# Sheet1.net
KiCad netlist of a schematic drawn in Altium Designer
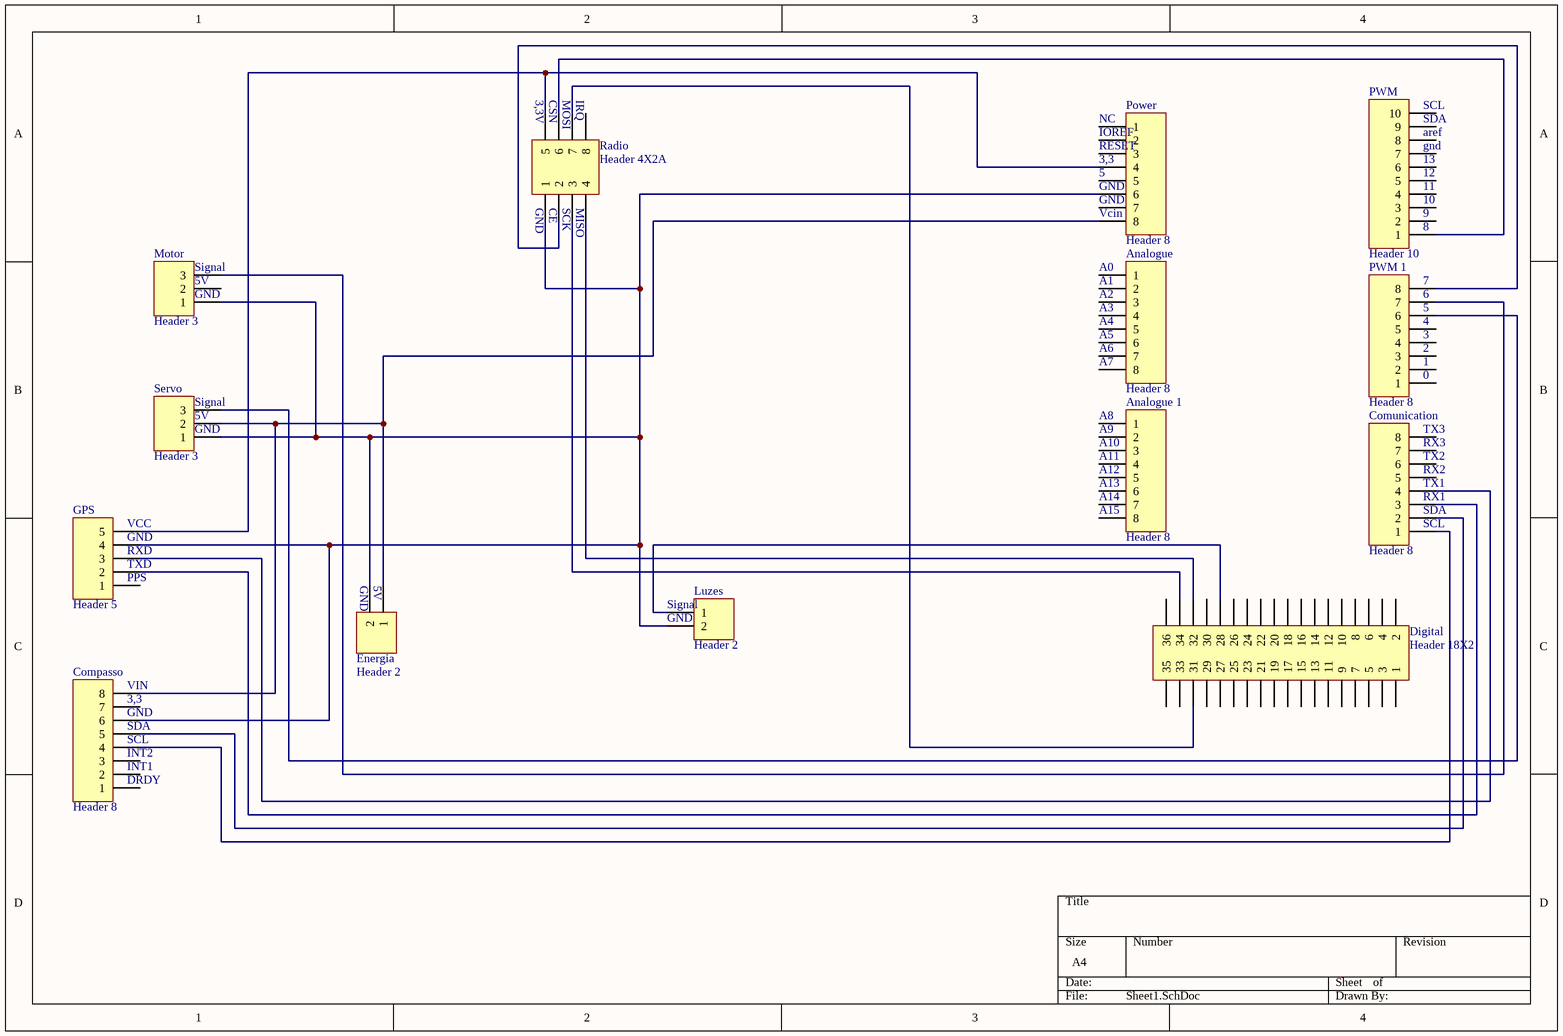
[diagram p0: Sheet1.SchDoc]

(export (version "E")
  (design (tool "Eeschema 10.0.6"))
  (components
    (comp (ref "Analogue")
      (value "Header 8")
      (footprint "HDR1X8")
      (description "Header, 8-Pin")
      (fields (field (name "PUBLISHER") "Altium Limited"))
      (libsource (lib "") (part "Header 8_1"))
    )
    (comp (ref "Analogue 1")
      (value "Header 8")
      (footprint "HDR1X8")
      (description "Header, 8-Pin")
      (fields (field (name "PUBLISHER") "Altium Limited"))
      (libsource (lib "") (part "Header 8_1"))
    )
    (comp (ref "Compasso")
      (value "Header 8")
      (footprint "HDR1X8")
      (description "Header, 8-Pin")
      (fields (field (name "PUBLISHER") "Altium Limited"))
      (libsource (lib "Miscellaneous Connectors") (part "Header 8"))
    )
    (comp (ref "Comunication")
      (value "Header 8")
      (footprint "HDR1X8")
      (description "Header, 8-Pin")
      (fields (field (name "PUBLISHER") "Altium Limited"))
      (libsource (lib "Miscellaneous Connectors") (part "Header 8"))
    )
    (comp (ref "Digital")
      (value "Header 18X2")
      (footprint "HDR2X18")
      (description "Header, 18-Pin, Dual row")
      (fields (field (name "PUBLISHER") "Altium Limited"))
      (libsource (lib "Miscellaneous Connectors") (part "Header 18X2"))
    )
    (comp (ref "Energia")
      (value "Header 2")
      (footprint "HDR1X2")
      (description "Header, 2-Pin")
      (fields (field (name "PUBLISHER") "Altium Limited"))
      (libsource (lib "") (part "Header 2_1"))
    )
    (comp (ref "GPS")
      (value "Header 5")
      (footprint "HDR1X5")
      (description "Header, 5-Pin")
      (fields (field (name "PUBLISHER") "Altium Limited"))
      (libsource (lib "Miscellaneous Connectors") (part "Header 5"))
    )
    (comp (ref "Luzes")
      (value "Header 2")
      (footprint "HDR1X2")
      (description "Header, 2-Pin")
      (fields (field (name "PUBLISHER") "Altium Limited"))
      (libsource (lib "Miscellaneous Connectors") (part "Header 2"))
    )
    (comp (ref "Motor")
      (value "Header 3")
      (footprint "HDR1X3")
      (description "Header, 3-Pin")
      (fields (field (name "PUBLISHER") "Altium Limited"))
      (libsource (lib "Miscellaneous Connectors") (part "Header 3"))
    )
    (comp (ref "Power")
      (value "Header 8")
      (footprint "HDR1X8")
      (description "Header, 8-Pin")
      (fields (field (name "PUBLISHER") "Altium Limited"))
      (libsource (lib "") (part "Header 8_1"))
    )
    (comp (ref "PWM")
      (value "Header 10")
      (footprint "HDR1X10")
      (description "Header, 10-Pin")
      (fields (field (name "PUBLISHER") "Altium Limited"))
      (libsource (lib "Miscellaneous Connectors") (part "Header 10"))
    )
    (comp (ref "PWM 1")
      (value "Header 8")
      (footprint "HDR1X8")
      (description "Header, 8-Pin")
      (fields (field (name "PUBLISHER") "Altium Limited"))
      (libsource (lib "Miscellaneous Connectors") (part "Header 8"))
    )
    (comp (ref "Radio")
      (value "Header 4X2A")
      (footprint "HDR2X4_CEN")
      (description "Header, 4-Pin, Dual row")
      (fields (field (name "PUBLISHER") "Altium Limited"))
      (libsource (lib "Miscellaneous Connectors") (part "Header 4X2A"))
    )
    (comp (ref "Servo")
      (value "Header 3")
      (footprint "HDR1X3")
      (description "Header, 3-Pin")
      (fields (field (name "PUBLISHER") "Altium Limited"))
      (libsource (lib "Miscellaneous Connectors") (part "Header 3"))
    )
  )
  (nets
    (net (code "1") (name "Net-(Compasso-Pad4)") (class "Default")
      (node (ref "Compasso") (pin "4") (pinfunction "4_4") (pintype "passive"))
      (node (ref "Comunication") (pin "1") (pinfunction "1_1") (pintype "passive"))
    )
    (net (code "2") (name "Net-(Compasso-Pad5)") (class "Default")
      (node (ref "Compasso") (pin "5") (pinfunction "5_5") (pintype "passive"))
      (node (ref "Comunication") (pin "2") (pinfunction "2_2") (pintype "passive"))
    )
    (net (code "3") (name "Net-(Compasso-Pad6)") (class "Default")
      (node (ref "Compasso") (pin "6") (pinfunction "6_6") (pintype "passive"))
      (node (ref "Energia") (pin "2") (pinfunction "2_2") (pintype "passive"))
      (node (ref "GPS") (pin "4") (pinfunction "4_4") (pintype "passive"))
      (node (ref "Luzes") (pin "2") (pinfunction "2_2") (pintype "passive"))
      (node (ref "Motor") (pin "1") (pinfunction "1_1") (pintype "passive"))
      (node (ref "Power") (pin "6") (pinfunction "6_6") (pintype "passive"))
      (node (ref "Radio") (pin "1") (pinfunction "1_1") (pintype "passive"))
      (node (ref "Servo") (pin "1") (pinfunction "1_1") (pintype "passive"))
    )
    (net (code "4") (name "Net-(Compasso-Pad8)") (class "Default")
      (node (ref "Compasso") (pin "8") (pinfunction "8_8") (pintype "passive"))
      (node (ref "Energia") (pin "1") (pinfunction "1_1") (pintype "passive"))
      (node (ref "Power") (pin "8") (pinfunction "8_8") (pintype "passive"))
      (node (ref "Servo") (pin "2") (pinfunction "2_2") (pintype "passive"))
    )
    (net (code "5") (name "Net-(Comunication-Pad3)") (class "Default")
      (node (ref "Comunication") (pin "3") (pinfunction "3_3") (pintype "passive"))
      (node (ref "GPS") (pin "2") (pinfunction "2_2") (pintype "passive"))
    )
    (net (code "6") (name "Net-(Comunication-Pad4)") (class "Default")
      (node (ref "Comunication") (pin "4") (pinfunction "4_4") (pintype "passive"))
      (node (ref "GPS") (pin "3") (pinfunction "3_3") (pintype "passive"))
    )
    (net (code "7") (name "Net-(Digital-Pad28)") (class "Default")
      (node (ref "Digital") (pin "28") (pinfunction "28_28") (pintype "passive"))
      (node (ref "Luzes") (pin "1") (pinfunction "1_1") (pintype "passive"))
    )
    (net (code "8") (name "Net-(Digital-Pad31)") (class "Default")
      (node (ref "Digital") (pin "31") (pinfunction "31_31") (pintype "passive"))
      (node (ref "Radio") (pin "7") (pinfunction "7_7") (pintype "passive"))
    )
    (net (code "9") (name "Net-(Digital-Pad32)") (class "Default")
      (node (ref "Digital") (pin "32") (pinfunction "32_32") (pintype "passive"))
      (node (ref "Radio") (pin "4") (pinfunction "4_4") (pintype "passive"))
    )
    (net (code "10") (name "Net-(Digital-Pad34)") (class "Default")
      (node (ref "Digital") (pin "34") (pinfunction "34_34") (pintype "passive"))
      (node (ref "Radio") (pin "3") (pinfunction "3_3") (pintype "passive"))
    )
    (net (code "11") (name "Net-(GPS-Pad5)") (class "Default")
      (node (ref "GPS") (pin "5") (pinfunction "5_5") (pintype "passive"))
      (node (ref "Power") (pin "4") (pinfunction "4_4") (pintype "passive"))
      (node (ref "Radio") (pin "5") (pinfunction "5_5") (pintype "passive"))
    )
    (net (code "12") (name "Net-(Motor-Pad3)") (class "Default")
      (node (ref "Motor") (pin "3") (pinfunction "3_3") (pintype "passive"))
      (node (ref "PWM 1") (pin "7") (pinfunction "7_7") (pintype "passive"))
    )
    (net (code "13") (name "Net-(PWM 1-Pad6)") (class "Default")
      (node (ref "PWM 1") (pin "6") (pinfunction "6_6") (pintype "passive"))
      (node (ref "Servo") (pin "3") (pinfunction "3_3") (pintype "passive"))
    )
    (net (code "14") (name "Net-(PWM 1-Pad8)") (class "Default")
      (node (ref "PWM 1") (pin "8") (pinfunction "8_8") (pintype "passive"))
      (node (ref "Radio") (pin "2") (pinfunction "2_2") (pintype "passive"))
    )
    (net (code "15") (name "Net-(PWM-Pad1)") (class "Default")
      (node (ref "PWM") (pin "1") (pinfunction "1_1") (pintype "passive"))
      (node (ref "Radio") (pin "6") (pinfunction "6_6") (pintype "passive"))
    )
    (net (code "16") (name "unconnected-(Analogue 1-Pad1)") (class "Default")
      (node (ref "Analogue 1") (pin "1") (pinfunction "1_1") (pintype "passive"))
    )
    (net (code "17") (name "unconnected-(Analogue 1-Pad2)") (class "Default")
      (node (ref "Analogue 1") (pin "2") (pinfunction "2_2") (pintype "passive"))
    )
    (net (code "18") (name "unconnected-(Analogue 1-Pad3)") (class "Default")
      (node (ref "Analogue 1") (pin "3") (pinfunction "3_3") (pintype "passive"))
    )
    (net (code "19") (name "unconnected-(Analogue 1-Pad4)") (class "Default")
      (node (ref "Analogue 1") (pin "4") (pinfunction "4_4") (pintype "passive"))
    )
    (net (code "20") (name "unconnected-(Analogue 1-Pad5)") (class "Default")
      (node (ref "Analogue 1") (pin "5") (pinfunction "5_5") (pintype "passive"))
    )
    (net (code "21") (name "unconnected-(Analogue 1-Pad6)") (class "Default")
      (node (ref "Analogue 1") (pin "6") (pinfunction "6_6") (pintype "passive"))
    )
    (net (code "22") (name "unconnected-(Analogue 1-Pad7)") (class "Default")
      (node (ref "Analogue 1") (pin "7") (pinfunction "7_7") (pintype "passive"))
    )
    (net (code "23") (name "unconnected-(Analogue 1-Pad8)") (class "Default")
      (node (ref "Analogue 1") (pin "8") (pinfunction "8_8") (pintype "passive"))
    )
    (net (code "24") (name "unconnected-(Analogue-Pad1)") (class "Default")
      (node (ref "Analogue") (pin "1") (pinfunction "1_1") (pintype "passive"))
    )
    (net (code "25") (name "unconnected-(Analogue-Pad2)") (class "Default")
      (node (ref "Analogue") (pin "2") (pinfunction "2_2") (pintype "passive"))
    )
    (net (code "26") (name "unconnected-(Analogue-Pad3)") (class "Default")
      (node (ref "Analogue") (pin "3") (pinfunction "3_3") (pintype "passive"))
    )
    (net (code "27") (name "unconnected-(Analogue-Pad4)") (class "Default")
      (node (ref "Analogue") (pin "4") (pinfunction "4_4") (pintype "passive"))
    )
    (net (code "28") (name "unconnected-(Analogue-Pad5)") (class "Default")
      (node (ref "Analogue") (pin "5") (pinfunction "5_5") (pintype "passive"))
    )
    (net (code "29") (name "unconnected-(Analogue-Pad6)") (class "Default")
      (node (ref "Analogue") (pin "6") (pinfunction "6_6") (pintype "passive"))
    )
    (net (code "30") (name "unconnected-(Analogue-Pad7)") (class "Default")
      (node (ref "Analogue") (pin "7") (pinfunction "7_7") (pintype "passive"))
    )
    (net (code "31") (name "unconnected-(Analogue-Pad8)") (class "Default")
      (node (ref "Analogue") (pin "8") (pinfunction "8_8") (pintype "passive"))
    )
    (net (code "32") (name "unconnected-(Compasso-Pad1)") (class "Default")
      (node (ref "Compasso") (pin "1") (pinfunction "1_1") (pintype "passive"))
    )
    (net (code "33") (name "unconnected-(Compasso-Pad2)") (class "Default")
      (node (ref "Compasso") (pin "2") (pinfunction "2_2") (pintype "passive"))
    )
    (net (code "34") (name "unconnected-(Compasso-Pad3)") (class "Default")
      (node (ref "Compasso") (pin "3") (pinfunction "3_3") (pintype "passive"))
    )
    (net (code "35") (name "unconnected-(Compasso-Pad7)") (class "Default")
      (node (ref "Compasso") (pin "7") (pinfunction "7_7") (pintype "passive"))
    )
    (net (code "36") (name "unconnected-(Comunication-Pad5)") (class "Default")
      (node (ref "Comunication") (pin "5") (pinfunction "5_5") (pintype "passive"))
    )
    (net (code "37") (name "unconnected-(Comunication-Pad6)") (class "Default")
      (node (ref "Comunication") (pin "6") (pinfunction "6_6") (pintype "passive"))
    )
    (net (code "38") (name "unconnected-(Comunication-Pad7)") (class "Default")
      (node (ref "Comunication") (pin "7") (pinfunction "7_7") (pintype "passive"))
    )
    (net (code "39") (name "unconnected-(Comunication-Pad8)") (class "Default")
      (node (ref "Comunication") (pin "8") (pinfunction "8_8") (pintype "passive"))
    )
    (net (code "40") (name "unconnected-(Digital-Pad1)") (class "Default")
      (node (ref "Digital") (pin "1") (pinfunction "1_1") (pintype "passive"))
    )
    (net (code "41") (name "unconnected-(Digital-Pad2)") (class "Default")
      (node (ref "Digital") (pin "2") (pinfunction "2_2") (pintype "passive"))
    )
    (net (code "42") (name "unconnected-(Digital-Pad3)") (class "Default")
      (node (ref "Digital") (pin "3") (pinfunction "3_3") (pintype "passive"))
    )
    (net (code "43") (name "unconnected-(Digital-Pad4)") (class "Default")
      (node (ref "Digital") (pin "4") (pinfunction "4_4") (pintype "passive"))
    )
    (net (code "44") (name "unconnected-(Digital-Pad5)") (class "Default")
      (node (ref "Digital") (pin "5") (pinfunction "5_5") (pintype "passive"))
    )
    (net (code "45") (name "unconnected-(Digital-Pad6)") (class "Default")
      (node (ref "Digital") (pin "6") (pinfunction "6_6") (pintype "passive"))
    )
    (net (code "46") (name "unconnected-(Digital-Pad7)") (class "Default")
      (node (ref "Digital") (pin "7") (pinfunction "7_7") (pintype "passive"))
    )
    (net (code "47") (name "unconnected-(Digital-Pad8)") (class "Default")
      (node (ref "Digital") (pin "8") (pinfunction "8_8") (pintype "passive"))
    )
    (net (code "48") (name "unconnected-(Digital-Pad9)") (class "Default")
      (node (ref "Digital") (pin "9") (pinfunction "9_9") (pintype "passive"))
    )
    (net (code "49") (name "unconnected-(Digital-Pad10)") (class "Default")
      (node (ref "Digital") (pin "10") (pinfunction "10_10") (pintype "passive"))
    )
    (net (code "50") (name "unconnected-(Digital-Pad11)") (class "Default")
      (node (ref "Digital") (pin "11") (pinfunction "11_11") (pintype "passive"))
    )
    (net (code "51") (name "unconnected-(Digital-Pad12)") (class "Default")
      (node (ref "Digital") (pin "12") (pinfunction "12_12") (pintype "passive"))
    )
    (net (code "52") (name "unconnected-(Digital-Pad13)") (class "Default")
      (node (ref "Digital") (pin "13") (pinfunction "13_13") (pintype "passive"))
    )
    (net (code "53") (name "unconnected-(Digital-Pad14)") (class "Default")
      (node (ref "Digital") (pin "14") (pinfunction "14_14") (pintype "passive"))
    )
    (net (code "54") (name "unconnected-(Digital-Pad15)") (class "Default")
      (node (ref "Digital") (pin "15") (pinfunction "15_15") (pintype "passive"))
    )
    (net (code "55") (name "unconnected-(Digital-Pad16)") (class "Default")
      (node (ref "Digital") (pin "16") (pinfunction "16_16") (pintype "passive"))
    )
    (net (code "56") (name "unconnected-(Digital-Pad17)") (class "Default")
      (node (ref "Digital") (pin "17") (pinfunction "17_17") (pintype "passive"))
    )
    (net (code "57") (name "unconnected-(Digital-Pad18)") (class "Default")
      (node (ref "Digital") (pin "18") (pinfunction "18_18") (pintype "passive"))
    )
    (net (code "58") (name "unconnected-(Digital-Pad19)") (class "Default")
      (node (ref "Digital") (pin "19") (pinfunction "19_19") (pintype "passive"))
    )
    (net (code "59") (name "unconnected-(Digital-Pad20)") (class "Default")
      (node (ref "Digital") (pin "20") (pinfunction "20_20") (pintype "passive"))
    )
    (net (code "60") (name "unconnected-(Digital-Pad21)") (class "Default")
      (node (ref "Digital") (pin "21") (pinfunction "21_21") (pintype "passive"))
    )
    (net (code "61") (name "unconnected-(Digital-Pad22)") (class "Default")
      (node (ref "Digital") (pin "22") (pinfunction "22_22") (pintype "passive"))
    )
    (net (code "62") (name "unconnected-(Digital-Pad23)") (class "Default")
      (node (ref "Digital") (pin "23") (pinfunction "23_23") (pintype "passive"))
    )
    (net (code "63") (name "unconnected-(Digital-Pad24)") (class "Default")
      (node (ref "Digital") (pin "24") (pinfunction "24_24") (pintype "passive"))
    )
    (net (code "64") (name "unconnected-(Digital-Pad25)") (class "Default")
      (node (ref "Digital") (pin "25") (pinfunction "25_25") (pintype "passive"))
    )
    (net (code "65") (name "unconnected-(Digital-Pad26)") (class "Default")
      (node (ref "Digital") (pin "26") (pinfunction "26_26") (pintype "passive"))
    )
    (net (code "66") (name "unconnected-(Digital-Pad27)") (class "Default")
      (node (ref "Digital") (pin "27") (pinfunction "27_27") (pintype "passive"))
    )
    (net (code "67") (name "unconnected-(Digital-Pad29)") (class "Default")
      (node (ref "Digital") (pin "29") (pinfunction "29_29") (pintype "passive"))
    )
    (net (code "68") (name "unconnected-(Digital-Pad30)") (class "Default")
      (node (ref "Digital") (pin "30") (pinfunction "30_30") (pintype "passive"))
    )
    (net (code "69") (name "unconnected-(Digital-Pad33)") (class "Default")
      (node (ref "Digital") (pin "33") (pinfunction "33_33") (pintype "passive"))
    )
    (net (code "70") (name "unconnected-(Digital-Pad35)") (class "Default")
      (node (ref "Digital") (pin "35") (pinfunction "35_35") (pintype "passive"))
    )
    (net (code "71") (name "unconnected-(Digital-Pad36)") (class "Default")
      (node (ref "Digital") (pin "36") (pinfunction "36_36") (pintype "passive"))
    )
    (net (code "72") (name "unconnected-(GPS-Pad1)") (class "Default")
      (node (ref "GPS") (pin "1") (pinfunction "1_1") (pintype "passive"))
    )
    (net (code "73") (name "unconnected-(Motor-Pad2)") (class "Default")
      (node (ref "Motor") (pin "2") (pinfunction "2_2") (pintype "passive"))
    )
    (net (code "74") (name "unconnected-(PWM 1-Pad1)") (class "Default")
      (node (ref "PWM 1") (pin "1") (pinfunction "1_1") (pintype "passive"))
    )
    (net (code "75") (name "unconnected-(PWM 1-Pad2)") (class "Default")
      (node (ref "PWM 1") (pin "2") (pinfunction "2_2") (pintype "passive"))
    )
    (net (code "76") (name "unconnected-(PWM 1-Pad3)") (class "Default")
      (node (ref "PWM 1") (pin "3") (pinfunction "3_3") (pintype "passive"))
    )
    (net (code "77") (name "unconnected-(PWM 1-Pad4)") (class "Default")
      (node (ref "PWM 1") (pin "4") (pinfunction "4_4") (pintype "passive"))
    )
    (net (code "78") (name "unconnected-(PWM 1-Pad5)") (class "Default")
      (node (ref "PWM 1") (pin "5") (pinfunction "5_5") (pintype "passive"))
    )
    (net (code "79") (name "unconnected-(PWM-Pad2)") (class "Default")
      (node (ref "PWM") (pin "2") (pinfunction "2_2") (pintype "passive"))
    )
    (net (code "80") (name "unconnected-(PWM-Pad3)") (class "Default")
      (node (ref "PWM") (pin "3") (pinfunction "3_3") (pintype "passive"))
    )
    (net (code "81") (name "unconnected-(PWM-Pad4)") (class "Default")
      (node (ref "PWM") (pin "4") (pinfunction "4_4") (pintype "passive"))
    )
    (net (code "82") (name "unconnected-(PWM-Pad5)") (class "Default")
      (node (ref "PWM") (pin "5") (pinfunction "5_5") (pintype "passive"))
    )
    (net (code "83") (name "unconnected-(PWM-Pad6)") (class "Default")
      (node (ref "PWM") (pin "6") (pinfunction "6_6") (pintype "passive"))
    )
    (net (code "84") (name "unconnected-(PWM-Pad7)") (class "Default")
      (node (ref "PWM") (pin "7") (pinfunction "7_7") (pintype "passive"))
    )
    (net (code "85") (name "unconnected-(PWM-Pad8)") (class "Default")
      (node (ref "PWM") (pin "8") (pinfunction "8_8") (pintype "passive"))
    )
    (net (code "86") (name "unconnected-(PWM-Pad9)") (class "Default")
      (node (ref "PWM") (pin "9") (pinfunction "9_9") (pintype "passive"))
    )
    (net (code "87") (name "unconnected-(PWM-Pad10)") (class "Default")
      (node (ref "PWM") (pin "10") (pinfunction "10_10") (pintype "passive"))
    )
    (net (code "88") (name "unconnected-(Power-Pad1)") (class "Default")
      (node (ref "Power") (pin "1") (pinfunction "1_1") (pintype "passive"))
    )
    (net (code "89") (name "unconnected-(Power-Pad2)") (class "Default")
      (node (ref "Power") (pin "2") (pinfunction "2_2") (pintype "passive"))
    )
    (net (code "90") (name "unconnected-(Power-Pad3)") (class "Default")
      (node (ref "Power") (pin "3") (pinfunction "3_3") (pintype "passive"))
    )
    (net (code "91") (name "unconnected-(Power-Pad5)") (class "Default")
      (node (ref "Power") (pin "5") (pinfunction "5_5") (pintype "passive"))
    )
    (net (code "92") (name "unconnected-(Power-Pad7)") (class "Default")
      (node (ref "Power") (pin "7") (pinfunction "7_7") (pintype "passive"))
    )
    (net (code "93") (name "unconnected-(Radio-Pad8)") (class "Default")
      (node (ref "Radio") (pin "8") (pinfunction "8_8") (pintype "passive"))
    )
  )
)
